# design.net
KiCad netlist of a schematic drawn in Altium Designer
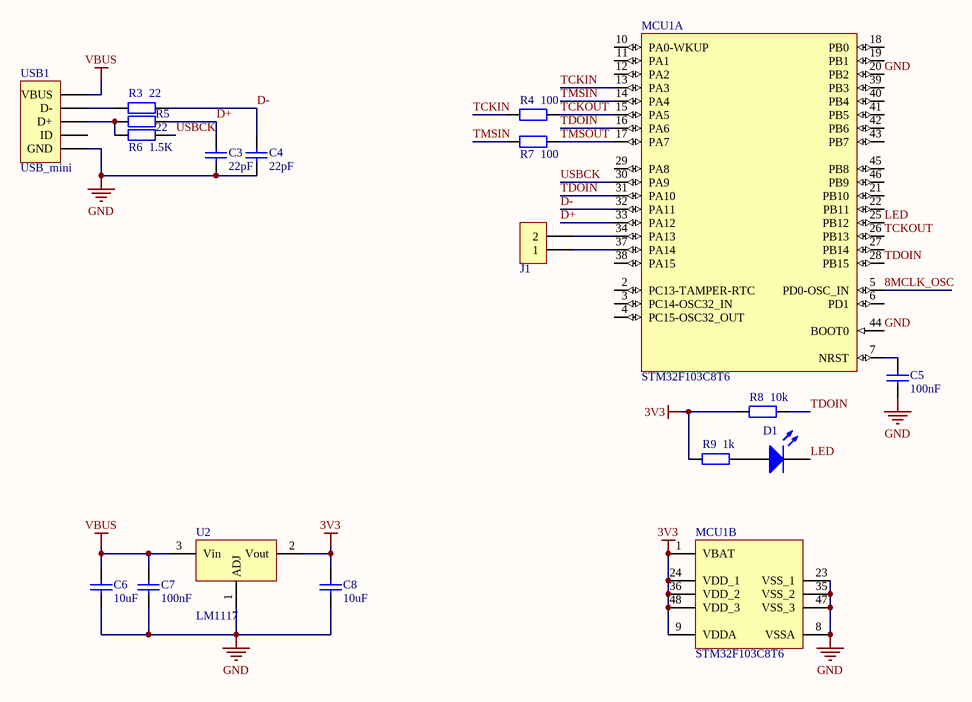
[diagram p0: 仿真器.SchDoc]

(export (version "E")
  (design (tool "Eeschema 10.0.6"))
  (components
    (comp (ref "C3")
      (value "22pF")
      (footprint "0805")
      (description "Capacitor")
      (fields (field (name "PUBLISHER") "Altium Limited"))
      (libsource (lib "yitiandelan") (part "Cap"))
    )
    (comp (ref "C4")
      (value "22pF")
      (footprint "0805")
      (description "Capacitor")
      (fields (field (name "PUBLISHER") "Altium Limited"))
      (libsource (lib "yitiandelan") (part "Cap"))
    )
    (comp (ref "C5")
      (value "100nF")
      (footprint "0805")
      (description "Capacitor")
      (fields (field (name "PUBLISHER") "Altium Limited"))
      (libsource (lib "yitiandelan") (part "Cap"))
    )
    (comp (ref "C6")
      (value "10uF")
      (footprint "0805")
      (description "Capacitor")
      (fields (field (name "PUBLISHER") "Altium Limited"))
      (libsource (lib "yitiandelan") (part "Cap"))
    )
    (comp (ref "C7")
      (value "100nF")
      (footprint "0805")
      (description "Capacitor")
      (fields (field (name "PUBLISHER") "Altium Limited"))
      (libsource (lib "yitiandelan") (part "Cap"))
    )
    (comp (ref "C8")
      (value "10uF")
      (footprint "0805")
      (description "Capacitor")
      (fields (field (name "PUBLISHER") "Altium Limited"))
      (libsource (lib "yitiandelan") (part "Cap"))
    )
    (comp (ref "D1")
      (value "LED0")
      (footprint "0805")
      (description "Typical INFRARED GaAs LED")
      (fields (field (name "PUBLISHER") "Altium Limited"))
      (libsource (lib "yitiandelan") (part "LED0"))
    )
    (comp (ref "J1")
      (value "CON2")
      (footprint "0603")
      (description "Connector")
      (libsource (lib "yitiandelan") (part "CON2"))
    )
    (comp (ref "MCU1")
      (value "STM32F103C8T6")
      (footprint "LQLFP48")
      (libsource (lib "yitiandelan") (part "STM32F103C8T6"))
    )
    (comp (ref "R3")
      (value "22")
      (footprint "0805")
      (description "Resistor")
      (fields (field (name "PUBLISHER") "Altium Limited"))
      (libsource (lib "yitiandelan") (part "Res2"))
    )
    (comp (ref "R4")
      (value "100")
      (footprint "0805")
      (description "Resistor")
      (fields (field (name "PUBLISHER") "Altium Limited"))
      (libsource (lib "yitiandelan") (part "Res2"))
    )
    (comp (ref "R5")
      (value "22")
      (footprint "0805")
      (description "Resistor")
      (fields (field (name "PUBLISHER") "Altium Limited"))
      (libsource (lib "yitiandelan") (part "Res2"))
    )
    (comp (ref "R6")
      (value "1.5K")
      (footprint "0805")
      (description "Resistor")
      (fields (field (name "PUBLISHER") "Altium Limited"))
      (libsource (lib "yitiandelan") (part "Res2"))
    )
    (comp (ref "R7")
      (value "100")
      (footprint "0805")
      (description "Resistor")
      (fields (field (name "PUBLISHER") "Altium Limited"))
      (libsource (lib "yitiandelan") (part "Res2"))
    )
    (comp (ref "R8")
      (value "10k")
      (footprint "0805")
      (description "Resistor")
      (fields (field (name "PUBLISHER") "Altium Limited"))
      (libsource (lib "") (part "Res2_1"))
    )
    (comp (ref "R9")
      (value "1k")
      (footprint "0805")
      (description "Resistor")
      (fields (field (name "PUBLISHER") "Altium Limited"))
      (libsource (lib "") (part "Res2_1"))
    )
    (comp (ref "U2")
      (value "LM1117")
      (footprint "SOT223_L")
      (description "正三端稳压器")
      (libsource (lib "yitiandelan") (part "LM1117"))
    )
    (comp (ref "USB1")
      (value "USB_mini")
      (footprint "USB-MICRO")
      (description "Connector")
      (libsource (lib "yitiandelan") (part "USB_mini"))
    )
  )
  (nets
    (net (code "1") (name "/8MCLK_OSC") (class "Default")
      (node (ref "MCU1") (pin "5") (pinfunction "PD0-OSC_IN_5") (pintype "bidirectional"))
    )
    (net (code "2") (name "/D+") (class "Default")
      (node (ref "C3") (pin "2") (pinfunction "2_2") (pintype "passive"))
      (node (ref "MCU1") (pin "33") (pinfunction "PA12_33") (pintype "bidirectional"))
      (node (ref "R5") (pin "2") (pinfunction "2_2") (pintype "passive"))
    )
    (net (code "3") (name "/D-") (class "Default")
      (node (ref "C4") (pin "2") (pinfunction "2_2") (pintype "passive"))
      (node (ref "MCU1") (pin "32") (pinfunction "PA11_32") (pintype "bidirectional"))
      (node (ref "R3") (pin "2") (pinfunction "2_2") (pintype "passive"))
    )
    (net (code "4") (name "/LED") (class "Default")
      (node (ref "D1") (pin "2") (pinfunction "K_2") (pintype "passive"))
      (node (ref "MCU1") (pin "25") (pinfunction "PB12_25") (pintype "bidirectional"))
    )
    (net (code "5") (name "/TCKIN") (class "Default")
      (node (ref "MCU1") (pin "13") (pinfunction "PA3_13") (pintype "bidirectional"))
      (node (ref "R4") (pin "1") (pinfunction "1_1") (pintype "passive"))
    )
    (net (code "6") (name "/TCKOUT") (class "Default")
      (node (ref "MCU1") (pin "15") (pinfunction "PA5_15") (pintype "bidirectional"))
      (node (ref "MCU1") (pin "26") (pinfunction "PB13_26") (pintype "bidirectional"))
      (node (ref "R4") (pin "2") (pinfunction "2_2") (pintype "passive"))
    )
    (net (code "7") (name "/TDOIN") (class "Default")
      (node (ref "MCU1") (pin "16") (pinfunction "PA6_16") (pintype "bidirectional"))
      (node (ref "MCU1") (pin "28") (pinfunction "PB15_28") (pintype "bidirectional"))
      (node (ref "MCU1") (pin "31") (pinfunction "PA10_31") (pintype "bidirectional"))
      (node (ref "R8") (pin "1") (pinfunction "1_1") (pintype "passive"))
    )
    (net (code "8") (name "/TMSIN") (class "Default")
      (node (ref "MCU1") (pin "14") (pinfunction "PA4_14") (pintype "bidirectional"))
      (node (ref "R7") (pin "1") (pinfunction "1_1") (pintype "passive"))
    )
    (net (code "9") (name "/TMSOUT") (class "Default")
      (node (ref "MCU1") (pin "17") (pinfunction "PA7_17") (pintype "bidirectional"))
      (node (ref "R7") (pin "2") (pinfunction "2_2") (pintype "passive"))
    )
    (net (code "10") (name "/USBCK") (class "Default")
      (node (ref "MCU1") (pin "30") (pinfunction "PA9_30") (pintype "bidirectional"))
      (node (ref "R6") (pin "2") (pinfunction "2_2") (pintype "passive"))
    )
    (net (code "11") (name "3V3") (class "Default")
      (node (ref "C8") (pin "1") (pinfunction "1_1") (pintype "passive"))
      (node (ref "MCU1") (pin "1") (pinfunction "VBAT_1") (pintype "power_in"))
      (node (ref "MCU1") (pin "24") (pinfunction "VDD_1_24") (pintype "power_in"))
      (node (ref "MCU1") (pin "36") (pinfunction "VDD_2_36") (pintype "power_in"))
      (node (ref "MCU1") (pin "48") (pinfunction "VDD_3_48") (pintype "power_in"))
      (node (ref "MCU1") (pin "9") (pinfunction "VDDA_9") (pintype "power_in"))
      (node (ref "R8") (pin "2") (pinfunction "2_2") (pintype "passive"))
      (node (ref "R9") (pin "2") (pinfunction "2_2") (pintype "passive"))
      (node (ref "U2") (pin "2") (pinfunction "Vout_2") (pintype "passive"))
    )
    (net (code "12") (name "GND") (class "Default")
      (node (ref "C3") (pin "1") (pinfunction "1_1") (pintype "passive"))
      (node (ref "C4") (pin "1") (pinfunction "1_1") (pintype "passive"))
      (node (ref "C5") (pin "2") (pinfunction "2_2") (pintype "passive"))
      (node (ref "C6") (pin "2") (pinfunction "2_2") (pintype "passive"))
      (node (ref "C7") (pin "1") (pinfunction "1_1") (pintype "passive"))
      (node (ref "C8") (pin "2") (pinfunction "2_2") (pintype "passive"))
      (node (ref "MCU1") (pin "20") (pinfunction "PB2_20") (pintype "bidirectional"))
      (node (ref "MCU1") (pin "23") (pinfunction "VSS_1_23") (pintype "power_in"))
      (node (ref "MCU1") (pin "35") (pinfunction "VSS_2_35") (pintype "power_in"))
      (node (ref "MCU1") (pin "44") (pinfunction "BOOT0_44") (pintype "input"))
      (node (ref "MCU1") (pin "47") (pinfunction "VSS_3_47") (pintype "power_in"))
      (node (ref "MCU1") (pin "8") (pinfunction "VSSA_8") (pintype "power_in"))
      (node (ref "U2") (pin "1") (pinfunction "ADJ_1") (pintype "passive"))
      (node (ref "USB1") (pin "5") (pinfunction "GND_5") (pintype "passive"))
    )
    (net (code "13") (name "Net-(D1-A)") (class "Default")
      (node (ref "D1") (pin "1") (pinfunction "A_1") (pintype "passive"))
      (node (ref "R9") (pin "1") (pinfunction "1_1") (pintype "passive"))
    )
    (net (code "14") (name "Net-(MCU1A-NRST)") (class "Default")
      (node (ref "C5") (pin "1") (pinfunction "1_1") (pintype "passive"))
      (node (ref "MCU1") (pin "7") (pinfunction "NRST_7") (pintype "bidirectional"))
    )
    (net (code "15") (name "Net-(MCU1A-PA13)") (class "Default")
      (node (ref "J1") (pin "2") (pinfunction "2_2") (pintype "passive"))
      (node (ref "MCU1") (pin "34") (pinfunction "PA13_34") (pintype "bidirectional"))
    )
    (net (code "16") (name "Net-(MCU1A-PA14)") (class "Default")
      (node (ref "J1") (pin "1") (pinfunction "1_1") (pintype "passive"))
      (node (ref "MCU1") (pin "37") (pinfunction "PA14_37") (pintype "bidirectional"))
    )
    (net (code "17") (name "Net-(USB1-D+)") (class "Default")
      (node (ref "R5") (pin "1") (pinfunction "1_1") (pintype "passive"))
      (node (ref "R6") (pin "1") (pinfunction "1_1") (pintype "passive"))
      (node (ref "USB1") (pin "3") (pinfunction "D+_3") (pintype "passive"))
    )
    (net (code "18") (name "Net-(USB1-D-)") (class "Default")
      (node (ref "R3") (pin "1") (pinfunction "1_1") (pintype "passive"))
      (node (ref "USB1") (pin "2") (pinfunction "D-_2") (pintype "passive"))
    )
    (net (code "19") (name "VBUS") (class "Default")
      (node (ref "C6") (pin "1") (pinfunction "1_1") (pintype "passive"))
      (node (ref "C7") (pin "2") (pinfunction "2_2") (pintype "passive"))
      (node (ref "U2") (pin "3") (pinfunction "Vin_3") (pintype "passive"))
      (node (ref "USB1") (pin "1") (pinfunction "VBUS_1") (pintype "passive"))
    )
    (net (code "20") (name "unconnected-(MCU1A-PA0-WKUP-Pad10)") (class "Default")
      (node (ref "MCU1") (pin "10") (pinfunction "PA0-WKUP_10") (pintype "bidirectional"))
    )
    (net (code "21") (name "unconnected-(MCU1A-PA1-Pad11)") (class "Default")
      (node (ref "MCU1") (pin "11") (pinfunction "PA1_11") (pintype "bidirectional"))
    )
    (net (code "22") (name "unconnected-(MCU1A-PA2-Pad12)") (class "Default")
      (node (ref "MCU1") (pin "12") (pinfunction "PA2_12") (pintype "bidirectional"))
    )
    (net (code "23") (name "unconnected-(MCU1A-PA8-Pad29)") (class "Default")
      (node (ref "MCU1") (pin "29") (pinfunction "PA8_29") (pintype "bidirectional"))
    )
    (net (code "24") (name "unconnected-(MCU1A-PA15-Pad38)") (class "Default")
      (node (ref "MCU1") (pin "38") (pinfunction "PA15_38") (pintype "bidirectional"))
    )
    (net (code "25") (name "unconnected-(MCU1A-PB0-Pad18)") (class "Default")
      (node (ref "MCU1") (pin "18") (pinfunction "PB0_18") (pintype "bidirectional"))
    )
    (net (code "26") (name "unconnected-(MCU1A-PB1-Pad19)") (class "Default")
      (node (ref "MCU1") (pin "19") (pinfunction "PB1_19") (pintype "bidirectional"))
    )
    (net (code "27") (name "unconnected-(MCU1A-PB3-Pad39)") (class "Default")
      (node (ref "MCU1") (pin "39") (pinfunction "PB3_39") (pintype "bidirectional"))
    )
    (net (code "28") (name "unconnected-(MCU1A-PB4-Pad40)") (class "Default")
      (node (ref "MCU1") (pin "40") (pinfunction "PB4_40") (pintype "bidirectional"))
    )
    (net (code "29") (name "unconnected-(MCU1A-PB5-Pad41)") (class "Default")
      (node (ref "MCU1") (pin "41") (pinfunction "PB5_41") (pintype "bidirectional"))
    )
    (net (code "30") (name "unconnected-(MCU1A-PB6-Pad42)") (class "Default")
      (node (ref "MCU1") (pin "42") (pinfunction "PB6_42") (pintype "bidirectional"))
    )
    (net (code "31") (name "unconnected-(MCU1A-PB7-Pad43)") (class "Default")
      (node (ref "MCU1") (pin "43") (pinfunction "PB7_43") (pintype "bidirectional"))
    )
    (net (code "32") (name "unconnected-(MCU1A-PB8-Pad45)") (class "Default")
      (node (ref "MCU1") (pin "45") (pinfunction "PB8_45") (pintype "bidirectional"))
    )
    (net (code "33") (name "unconnected-(MCU1A-PB9-Pad46)") (class "Default")
      (node (ref "MCU1") (pin "46") (pinfunction "PB9_46") (pintype "bidirectional"))
    )
    (net (code "34") (name "unconnected-(MCU1A-PB10-Pad21)") (class "Default")
      (node (ref "MCU1") (pin "21") (pinfunction "PB10_21") (pintype "bidirectional"))
    )
    (net (code "35") (name "unconnected-(MCU1A-PB11-Pad22)") (class "Default")
      (node (ref "MCU1") (pin "22") (pinfunction "PB11_22") (pintype "bidirectional"))
    )
    (net (code "36") (name "unconnected-(MCU1A-PB14-Pad27)") (class "Default")
      (node (ref "MCU1") (pin "27") (pinfunction "PB14_27") (pintype "bidirectional"))
    )
    (net (code "37") (name "unconnected-(MCU1A-PC13-TAMPER-RTC-Pad2)") (class "Default")
      (node (ref "MCU1") (pin "2") (pinfunction "PC13-TAMPER-RTC_2") (pintype "bidirectional"))
    )
    (net (code "38") (name "unconnected-(MCU1A-PC14-OSC32_IN-Pad3)") (class "Default")
      (node (ref "MCU1") (pin "3") (pinfunction "PC14-OSC32_IN_3") (pintype "bidirectional"))
    )
    (net (code "39") (name "unconnected-(MCU1A-PC15-OSC32_OUT-Pad4)") (class "Default")
      (node (ref "MCU1") (pin "4") (pinfunction "PC15-OSC32_OUT_4") (pintype "bidirectional"))
    )
    (net (code "40") (name "unconnected-(MCU1A-PD1-Pad6)") (class "Default")
      (node (ref "MCU1") (pin "6") (pinfunction "PD1_6") (pintype "bidirectional"))
    )
    (net (code "41") (name "unconnected-(USB1-ID-Pad4)") (class "Default")
      (node (ref "USB1") (pin "4") (pinfunction "ID_4") (pintype "passive"))
    )
  )
)
